# OUTPUT_UNIT.net
KiCad netlist of a schematic drawn in EAGLE
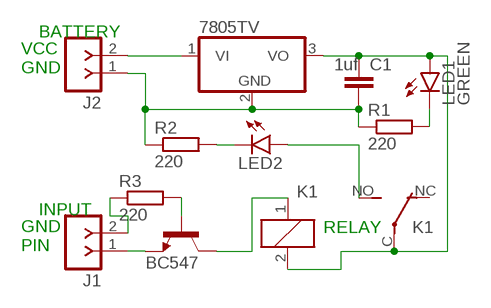
[diagram p0: schematic, sheet 1]

(export (version "E")
  (design (tool "Eeschema 10.0.6"))
  (components
    (comp (ref "C1")
      (value "1uf")
      (footprint "eagle-import:C025-025X050")
      (libsource (lib "eagle-import") (part "C-EU025-025X050"))
    )
    (comp (ref "IC1")
      (value "7805TV")
      (footprint "eagle-import:TO220V")
      (libsource (lib "eagle-import") (part "78TV05"))
    )
    (comp (ref "J1")
      (value "F-1X02-SIP-100-32Y")
      (footprint "eagle-import:SIP-100-02-32Y")
      (libsource (lib "eagle-import") (part "F-1X02-SIP-100-32Y"))
    )
    (comp (ref "J2")
      (value "F-1X02-SIP-100-32Y")
      (footprint "eagle-import:SIP-100-02-32Y")
      (libsource (lib "eagle-import") (part "F-1X02-SIP-100-32Y"))
    )
    (comp (ref "K1")
      (value "CQ1-12V")
      (footprint "eagle-import:CQ1")
      (libsource (lib "eagle-import") (part "CQ1-12V"))
    )
    (comp (ref "LED1")
      (value "GREEN")
      (footprint "eagle-import:SML1206")
      (libsource (lib "eagle-import") (part "LEDSML1206"))
    )
    (comp (ref "LED2")
      (value "RED")
      (footprint "eagle-import:LED5MM")
      (libsource (lib "eagle-import") (part "LED5MM"))
    )
    (comp (ref "R1")
      (value "220")
      (footprint "eagle-import:0204_7")
      (libsource (lib "eagle-import") (part "R-EU_0204/7"))
    )
    (comp (ref "R2")
      (value "220")
      (footprint "eagle-import:0204_7")
      (libsource (lib "eagle-import") (part "R-EU_0204/7"))
    )
    (comp (ref "R3")
      (value "220")
      (footprint "eagle-import:0204_7")
      (libsource (lib "eagle-import") (part "R-EU_0204/7"))
    )
    (comp (ref "T1")
      (value "BC547")
      (footprint "eagle-import:TO92")
      (libsource (lib "eagle-import") (part "BC547"))
    )
  )
  (nets
    (net (code "1") (name "Net-(IC1-GND)") (class "Default")
      (node (ref "C1") (pin "2") (pinfunction "2_2") (pintype "passive"))
      (node (ref "IC1") (pin "2") (pinfunction "GND_2") (pintype "passive"))
      (node (ref "J2") (pin "1") (pinfunction "1_1") (pintype "passive"))
      (node (ref "R1") (pin "1") (pinfunction "1_1") (pintype "passive"))
      (node (ref "R2") (pin "1") (pinfunction "1_1") (pintype "passive"))
    )
    (net (code "2") (name "Net-(IC1-VI)") (class "Default")
      (node (ref "IC1") (pin "1") (pinfunction "VI_1") (pintype "input"))
      (node (ref "J2") (pin "2") (pinfunction "2_2") (pintype "passive"))
    )
    (net (code "3") (name "Net-(IC1-VO)") (class "Default")
      (node (ref "C1") (pin "1") (pinfunction "1_1") (pintype "passive"))
      (node (ref "IC1") (pin "3") (pinfunction "VO_3") (pintype "passive"))
      (node (ref "K1") (pin "2") (pinfunction "2_2") (pintype "passive"))
      (node (ref "K1") (pin "C") (pinfunction "P_C") (pintype "passive"))
      (node (ref "LED1") (pin "A") (pinfunction "A_A") (pintype "passive"))
    )
    (net (code "4") (name "Net-(J1-Pad2)") (class "Default")
      (node (ref "J1") (pin "2") (pinfunction "2_2") (pintype "passive"))
      (node (ref "R3") (pin "1") (pinfunction "1_1") (pintype "passive"))
    )
    (net (code "5") (name "Net-(K1B-S)") (class "Default")
      (node (ref "K1") (pin "NO") (pinfunction "S_NO") (pintype "passive"))
      (node (ref "LED2") (pin "A") (pinfunction "A_A") (pintype "passive"))
    )
    (net (code "6") (name "Net-(LED1-PadC)") (class "Default")
      (node (ref "LED1") (pin "C") (pinfunction "C_C") (pintype "passive"))
      (node (ref "R1") (pin "2") (pinfunction "2_2") (pintype "passive"))
    )
    (net (code "7") (name "Net-(LED2-C)") (class "Default")
      (node (ref "LED2") (pin "K") (pinfunction "C_K") (pintype "passive"))
      (node (ref "R2") (pin "2") (pinfunction "2_2") (pintype "passive"))
    )
    (net (code "8") (name "Net-(T1-B)") (class "Default")
      (node (ref "R3") (pin "2") (pinfunction "2_2") (pintype "passive"))
      (node (ref "T1") (pin "2") (pinfunction "B_2") (pintype "passive"))
    )
    (net (code "9") (name "Net-(T1-C)") (class "Default")
      (node (ref "K1") (pin "1") (pinfunction "1_1") (pintype "passive"))
      (node (ref "T1") (pin "3") (pinfunction "C_3") (pintype "passive"))
    )
    (net (code "10") (name "Net-(T1-E)") (class "Default")
      (node (ref "J1") (pin "1") (pinfunction "1_1") (pintype "passive"))
      (node (ref "T1") (pin "1") (pinfunction "E_1") (pintype "passive"))
    )
    (net (code "11") (name "unconnected-(K1B-O-PadNC)") (class "Default")
      (node (ref "K1") (pin "NC") (pinfunction "O_NC") (pintype "passive"))
    )
  )
)
